# Display.net
KiCad netlist of a schematic drawn in Altium Designer
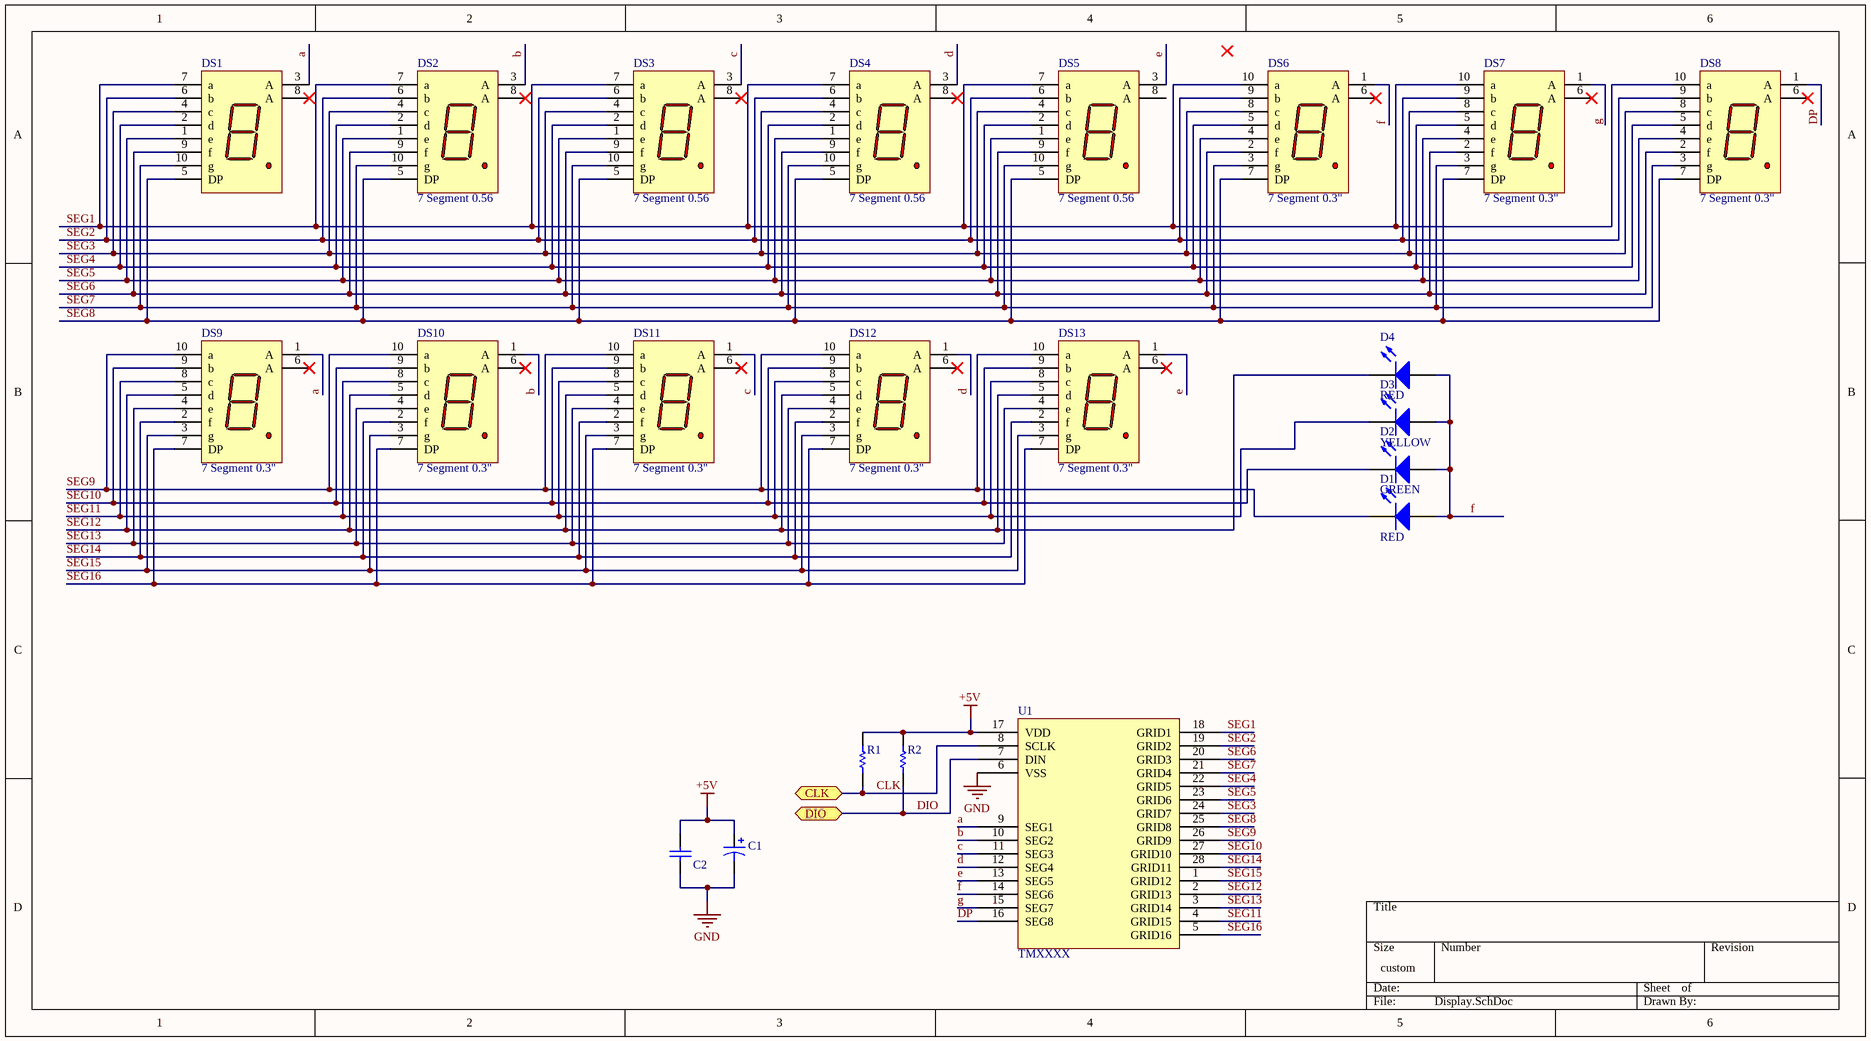
[diagram p0: Display.SchDoc]

(export (version "E")
  (design (tool "Eeschema 10.0.6"))
  (components
    (comp (ref "C1")
      (value "100uF/10V")
      (footprint "C10uF25V")
      (libsource (lib "Ravi") (part "Capacitor_Electrolytic"))
    )
    (comp (ref "C2")
      (value "0.1uF/10V")
      (footprint "C0603")
      (libsource (lib "Devices") (part "Capacitor_Ceramic"))
    )
    (comp (ref "D1") (value "RED") (footprint "LED-5mm") (libsource (lib "Ravi") (part "LED")))
    (comp (ref "D2") (value "GREEN") (footprint "LED-5mm") (libsource (lib "Ravi") (part "LED")))
    (comp (ref "D3") (value "YELLOW") (footprint "LED-5mm") (libsource (lib "Ravi") (part "LED")))
    (comp (ref "D4") (value "RED") (footprint "LED-5mm") (libsource (lib "Ravi") (part "LED")))
    (comp (ref "DS1")
      (value "7 Segment 0.56")
      (footprint "7Segment(0.56)")
      (libsource (lib "Ravi") (part "7 Segment_CA_0.56"))
    )
    (comp (ref "DS2")
      (value "7 Segment 0.56")
      (footprint "7Segment(0.56)")
      (libsource (lib "Ravi") (part "7 Segment_CA_0.56"))
    )
    (comp (ref "DS3")
      (value "7 Segment 0.56")
      (footprint "7Segment(0.56)")
      (libsource (lib "Ravi") (part "7 Segment_CA_0.56"))
    )
    (comp (ref "DS4")
      (value "7 Segment 0.56")
      (footprint "7Segment(0.56)")
      (libsource (lib "Ravi") (part "7 Segment_CA_0.56"))
    )
    (comp (ref "DS5")
      (value "7 Segment 0.56")
      (footprint "7Segment(0.56)")
      (libsource (lib "Ravi") (part "7 Segment_CA_0.56"))
    )
    (comp (ref "DS6")
      (value "7 Segment 0.3\"")
      (footprint "7Segment(0.36)")
      (libsource (lib "Ravi") (part "7 Segment_CA_0.36"))
    )
    (comp (ref "DS7")
      (value "7 Segment 0.3\"")
      (footprint "7Segment(0.36)")
      (libsource (lib "Ravi") (part "7 Segment_CA_0.36"))
    )
    (comp (ref "DS8")
      (value "7 Segment 0.3\"")
      (footprint "7Segment(0.36)")
      (libsource (lib "Ravi") (part "7 Segment_CA_0.36"))
    )
    (comp (ref "DS9")
      (value "7 Segment 0.3\"")
      (footprint "7Segment(0.36)")
      (libsource (lib "Ravi") (part "7 Segment_CA_0.36"))
    )
    (comp (ref "DS10")
      (value "7 Segment 0.3\"")
      (footprint "7Segment(0.36)")
      (libsource (lib "Ravi") (part "7 Segment_CA_0.36"))
    )
    (comp (ref "DS11")
      (value "7 Segment 0.3\"")
      (footprint "7Segment(0.36)")
      (libsource (lib "Ravi") (part "7 Segment_CA_0.36"))
    )
    (comp (ref "DS12")
      (value "7 Segment 0.3\"")
      (footprint "7Segment(0.36)")
      (libsource (lib "Ravi") (part "7 Segment_CA_0.36"))
    )
    (comp (ref "DS13")
      (value "7 Segment 0.3\"")
      (footprint "7Segment(0.36)")
      (libsource (lib "Ravi") (part "7 Segment_CA_0.36"))
    )
    (comp (ref "R1")
      (value "10K")
      (footprint "R0603")
      (description "Resistor")
      (fields (field (name "PUBLISHER") "Altium Limited"))
      (libsource (lib "Ravi") (part "Res1"))
    )
    (comp (ref "R2")
      (value "10K")
      (footprint "R0603")
      (description "Resistor")
      (fields (field (name "PUBLISHER") "Altium Limited"))
      (libsource (lib "Ravi") (part "Res1"))
    )
    (comp (ref "U1") (value "TMXXXX") (footprint "SOP28") (libsource (lib "Ravi") (part "TMXXXX")))
  )
  (nets
    (net (code "1") (name "+5V") (class "Default")
      (node (ref "C1") (pin "1") (pinfunction "1_1") (pintype "passive"))
      (node (ref "C2") (pin "2") (pinfunction "2_2") (pintype "passive"))
      (node (ref "R1") (pin "2") (pinfunction "2_2") (pintype "passive"))
      (node (ref "R2") (pin "2") (pinfunction "2_2") (pintype "passive"))
      (node (ref "U1") (pin "17") (pinfunction "VDD_17") (pintype "power_in"))
    )
    (net (code "2") (name "/CLK") (class "Default")
      (node (ref "R1") (pin "1") (pinfunction "1_1") (pintype "passive"))
      (node (ref "U1") (pin "8") (pinfunction "SCLK_8") (pintype "passive"))
    )
    (net (code "3") (name "/DIO") (class "Default")
      (node (ref "R2") (pin "1") (pinfunction "1_1") (pintype "passive"))
      (node (ref "U1") (pin "7") (pinfunction "DIN_7") (pintype "passive"))
    )
    (net (code "4") (name "/DP") (class "Default")
      (node (ref "DS8") (pin "1") (pinfunction "A_1") (pintype "passive"))
      (node (ref "U1") (pin "16") (pinfunction "SEG8_16") (pintype "open_collector"))
    )
    (net (code "5") (name "/SEG1") (class "Default")
      (node (ref "DS1") (pin "7") (pinfunction "a_7") (pintype "passive"))
      (node (ref "DS2") (pin "7") (pinfunction "a_7") (pintype "passive"))
      (node (ref "DS3") (pin "7") (pinfunction "a_7") (pintype "passive"))
      (node (ref "DS4") (pin "7") (pinfunction "a_7") (pintype "passive"))
      (node (ref "DS5") (pin "7") (pinfunction "a_7") (pintype "passive"))
      (node (ref "DS6") (pin "10") (pinfunction "a_10") (pintype "passive"))
      (node (ref "DS7") (pin "10") (pinfunction "a_10") (pintype "passive"))
      (node (ref "DS8") (pin "10") (pinfunction "a_10") (pintype "passive"))
      (node (ref "U1") (pin "18") (pinfunction "GRID1_18") (pintype "open_collector"))
    )
    (net (code "6") (name "/SEG2") (class "Default")
      (node (ref "DS1") (pin "6") (pinfunction "b_6") (pintype "passive"))
      (node (ref "DS2") (pin "6") (pinfunction "b_6") (pintype "passive"))
      (node (ref "DS3") (pin "6") (pinfunction "b_6") (pintype "passive"))
      (node (ref "DS4") (pin "6") (pinfunction "b_6") (pintype "passive"))
      (node (ref "DS5") (pin "6") (pinfunction "b_6") (pintype "passive"))
      (node (ref "DS6") (pin "9") (pinfunction "b_9") (pintype "passive"))
      (node (ref "DS7") (pin "9") (pinfunction "b_9") (pintype "passive"))
      (node (ref "DS8") (pin "9") (pinfunction "b_9") (pintype "passive"))
      (node (ref "U1") (pin "19") (pinfunction "GRID2_19") (pintype "open_collector"))
    )
    (net (code "7") (name "/SEG3") (class "Default")
      (node (ref "DS1") (pin "4") (pinfunction "c_4") (pintype "passive"))
      (node (ref "DS2") (pin "4") (pinfunction "c_4") (pintype "passive"))
      (node (ref "DS3") (pin "4") (pinfunction "c_4") (pintype "passive"))
      (node (ref "DS4") (pin "4") (pinfunction "c_4") (pintype "passive"))
      (node (ref "DS5") (pin "4") (pinfunction "c_4") (pintype "passive"))
      (node (ref "DS6") (pin "8") (pinfunction "c_8") (pintype "passive"))
      (node (ref "DS7") (pin "8") (pinfunction "c_8") (pintype "passive"))
      (node (ref "DS8") (pin "8") (pinfunction "c_8") (pintype "passive"))
      (node (ref "U1") (pin "24") (pinfunction "GRID7_24") (pintype "open_collector"))
    )
    (net (code "8") (name "/SEG4") (class "Default")
      (node (ref "DS1") (pin "2") (pinfunction "d_2") (pintype "passive"))
      (node (ref "DS2") (pin "2") (pinfunction "d_2") (pintype "passive"))
      (node (ref "DS3") (pin "2") (pinfunction "d_2") (pintype "passive"))
      (node (ref "DS4") (pin "2") (pinfunction "d_2") (pintype "passive"))
      (node (ref "DS5") (pin "2") (pinfunction "d_2") (pintype "passive"))
      (node (ref "DS6") (pin "5") (pinfunction "d_5") (pintype "passive"))
      (node (ref "DS7") (pin "5") (pinfunction "d_5") (pintype "passive"))
      (node (ref "DS8") (pin "5") (pinfunction "d_5") (pintype "passive"))
      (node (ref "U1") (pin "22") (pinfunction "GRID5_22") (pintype "open_collector"))
    )
    (net (code "9") (name "/SEG5") (class "Default")
      (node (ref "DS1") (pin "1") (pinfunction "e_1") (pintype "passive"))
      (node (ref "DS2") (pin "1") (pinfunction "e_1") (pintype "passive"))
      (node (ref "DS3") (pin "1") (pinfunction "e_1") (pintype "passive"))
      (node (ref "DS4") (pin "1") (pinfunction "e_1") (pintype "passive"))
      (node (ref "DS5") (pin "1") (pinfunction "e_1") (pintype "passive"))
      (node (ref "DS6") (pin "4") (pinfunction "e_4") (pintype "passive"))
      (node (ref "DS7") (pin "4") (pinfunction "e_4") (pintype "passive"))
      (node (ref "DS8") (pin "4") (pinfunction "e_4") (pintype "passive"))
      (node (ref "U1") (pin "23") (pinfunction "GRID6_23") (pintype "open_collector"))
    )
    (net (code "10") (name "/SEG6") (class "Default")
      (node (ref "DS1") (pin "9") (pinfunction "f_9") (pintype "passive"))
      (node (ref "DS2") (pin "9") (pinfunction "f_9") (pintype "passive"))
      (node (ref "DS3") (pin "9") (pinfunction "f_9") (pintype "passive"))
      (node (ref "DS4") (pin "9") (pinfunction "f_9") (pintype "passive"))
      (node (ref "DS5") (pin "9") (pinfunction "f_9") (pintype "passive"))
      (node (ref "DS6") (pin "2") (pinfunction "f_2") (pintype "passive"))
      (node (ref "DS7") (pin "2") (pinfunction "f_2") (pintype "passive"))
      (node (ref "DS8") (pin "2") (pinfunction "f_2") (pintype "passive"))
      (node (ref "U1") (pin "20") (pinfunction "GRID3_20") (pintype "open_collector"))
    )
    (net (code "11") (name "/SEG7") (class "Default")
      (node (ref "DS1") (pin "10") (pinfunction "g_10") (pintype "passive"))
      (node (ref "DS2") (pin "10") (pinfunction "g_10") (pintype "passive"))
      (node (ref "DS3") (pin "10") (pinfunction "g_10") (pintype "passive"))
      (node (ref "DS4") (pin "10") (pinfunction "g_10") (pintype "passive"))
      (node (ref "DS5") (pin "10") (pinfunction "g_10") (pintype "passive"))
      (node (ref "DS6") (pin "3") (pinfunction "g_3") (pintype "passive"))
      (node (ref "DS7") (pin "3") (pinfunction "g_3") (pintype "passive"))
      (node (ref "DS8") (pin "3") (pinfunction "g_3") (pintype "passive"))
      (node (ref "U1") (pin "21") (pinfunction "GRID4_21") (pintype "open_collector"))
    )
    (net (code "12") (name "/SEG8") (class "Default")
      (node (ref "DS1") (pin "5") (pinfunction "DP_5") (pintype "passive"))
      (node (ref "DS2") (pin "5") (pinfunction "DP_5") (pintype "passive"))
      (node (ref "DS3") (pin "5") (pinfunction "DP_5") (pintype "passive"))
      (node (ref "DS4") (pin "5") (pinfunction "DP_5") (pintype "passive"))
      (node (ref "DS5") (pin "5") (pinfunction "DP_5") (pintype "passive"))
      (node (ref "DS6") (pin "7") (pinfunction "DP_7") (pintype "passive"))
      (node (ref "DS7") (pin "7") (pinfunction "DP_7") (pintype "passive"))
      (node (ref "DS8") (pin "7") (pinfunction "DP_7") (pintype "passive"))
      (node (ref "U1") (pin "25") (pinfunction "GRID8_25") (pintype "open_collector"))
    )
    (net (code "13") (name "/SEG9") (class "Default")
      (node (ref "D1") (pin "2") (pinfunction "K_2") (pintype "passive"))
      (node (ref "DS10") (pin "10") (pinfunction "a_10") (pintype "passive"))
      (node (ref "DS11") (pin "10") (pinfunction "a_10") (pintype "passive"))
      (node (ref "DS12") (pin "10") (pinfunction "a_10") (pintype "passive"))
      (node (ref "DS13") (pin "10") (pinfunction "a_10") (pintype "passive"))
      (node (ref "DS9") (pin "10") (pinfunction "a_10") (pintype "passive"))
      (node (ref "U1") (pin "26") (pinfunction "GRID9_26") (pintype "open_collector"))
    )
    (net (code "14") (name "/SEG10") (class "Default")
      (node (ref "D2") (pin "2") (pinfunction "K_2") (pintype "passive"))
      (node (ref "DS10") (pin "9") (pinfunction "b_9") (pintype "passive"))
      (node (ref "DS11") (pin "9") (pinfunction "b_9") (pintype "passive"))
      (node (ref "DS12") (pin "9") (pinfunction "b_9") (pintype "passive"))
      (node (ref "DS13") (pin "9") (pinfunction "b_9") (pintype "passive"))
      (node (ref "DS9") (pin "9") (pinfunction "b_9") (pintype "passive"))
      (node (ref "U1") (pin "27") (pinfunction "GRID10_27") (pintype "open_collector"))
    )
    (net (code "15") (name "/SEG11") (class "Default")
      (node (ref "D3") (pin "2") (pinfunction "K_2") (pintype "passive"))
      (node (ref "DS10") (pin "8") (pinfunction "c_8") (pintype "passive"))
      (node (ref "DS11") (pin "8") (pinfunction "c_8") (pintype "passive"))
      (node (ref "DS12") (pin "8") (pinfunction "c_8") (pintype "passive"))
      (node (ref "DS13") (pin "8") (pinfunction "c_8") (pintype "passive"))
      (node (ref "DS9") (pin "8") (pinfunction "c_8") (pintype "passive"))
      (node (ref "U1") (pin "4") (pinfunction "GRID15_4") (pintype "open_collector"))
    )
    (net (code "16") (name "/SEG12") (class "Default")
      (node (ref "D4") (pin "2") (pinfunction "K_2") (pintype "passive"))
      (node (ref "DS10") (pin "5") (pinfunction "d_5") (pintype "passive"))
      (node (ref "DS11") (pin "5") (pinfunction "d_5") (pintype "passive"))
      (node (ref "DS12") (pin "5") (pinfunction "d_5") (pintype "passive"))
      (node (ref "DS13") (pin "5") (pinfunction "d_5") (pintype "passive"))
      (node (ref "DS9") (pin "5") (pinfunction "d_5") (pintype "passive"))
      (node (ref "U1") (pin "2") (pinfunction "GRID13_2") (pintype "open_collector"))
    )
    (net (code "17") (name "/SEG13") (class "Default")
      (node (ref "DS10") (pin "4") (pinfunction "e_4") (pintype "passive"))
      (node (ref "DS11") (pin "4") (pinfunction "e_4") (pintype "passive"))
      (node (ref "DS12") (pin "4") (pinfunction "e_4") (pintype "passive"))
      (node (ref "DS13") (pin "4") (pinfunction "e_4") (pintype "passive"))
      (node (ref "DS9") (pin "4") (pinfunction "e_4") (pintype "passive"))
      (node (ref "U1") (pin "3") (pinfunction "GRID14_3") (pintype "open_collector"))
    )
    (net (code "18") (name "/SEG14") (class "Default")
      (node (ref "DS10") (pin "2") (pinfunction "f_2") (pintype "passive"))
      (node (ref "DS11") (pin "2") (pinfunction "f_2") (pintype "passive"))
      (node (ref "DS12") (pin "2") (pinfunction "f_2") (pintype "passive"))
      (node (ref "DS13") (pin "2") (pinfunction "f_2") (pintype "passive"))
      (node (ref "DS9") (pin "2") (pinfunction "f_2") (pintype "passive"))
      (node (ref "U1") (pin "28") (pinfunction "GRID11_28") (pintype "open_collector"))
    )
    (net (code "19") (name "/SEG15") (class "Default")
      (node (ref "DS10") (pin "3") (pinfunction "g_3") (pintype "passive"))
      (node (ref "DS11") (pin "3") (pinfunction "g_3") (pintype "passive"))
      (node (ref "DS12") (pin "3") (pinfunction "g_3") (pintype "passive"))
      (node (ref "DS13") (pin "3") (pinfunction "g_3") (pintype "passive"))
      (node (ref "DS9") (pin "3") (pinfunction "g_3") (pintype "passive"))
      (node (ref "U1") (pin "1") (pinfunction "GRID12_1") (pintype "open_collector"))
    )
    (net (code "20") (name "/SEG16") (class "Default")
      (node (ref "DS10") (pin "7") (pinfunction "DP_7") (pintype "passive"))
      (node (ref "DS11") (pin "7") (pinfunction "DP_7") (pintype "passive"))
      (node (ref "DS12") (pin "7") (pinfunction "DP_7") (pintype "passive"))
      (node (ref "DS13") (pin "7") (pinfunction "DP_7") (pintype "passive"))
      (node (ref "DS9") (pin "7") (pinfunction "DP_7") (pintype "passive"))
      (node (ref "U1") (pin "5") (pinfunction "GRID16_5") (pintype "open_collector"))
    )
    (net (code "21") (name "/a") (class "Default")
      (node (ref "DS1") (pin "3") (pinfunction "A_3") (pintype "passive"))
      (node (ref "DS9") (pin "1") (pinfunction "A_1") (pintype "passive"))
      (node (ref "U1") (pin "9") (pinfunction "SEG1_9") (pintype "open_collector"))
    )
    (net (code "22") (name "/b") (class "Default")
      (node (ref "DS10") (pin "1") (pinfunction "A_1") (pintype "passive"))
      (node (ref "DS2") (pin "3") (pinfunction "A_3") (pintype "passive"))
      (node (ref "U1") (pin "10") (pinfunction "SEG2_10") (pintype "open_collector"))
    )
    (net (code "23") (name "/c") (class "Default")
      (node (ref "DS11") (pin "1") (pinfunction "A_1") (pintype "passive"))
      (node (ref "DS3") (pin "3") (pinfunction "A_3") (pintype "passive"))
      (node (ref "U1") (pin "11") (pinfunction "SEG3_11") (pintype "open_collector"))
    )
    (net (code "24") (name "/d") (class "Default")
      (node (ref "DS12") (pin "1") (pinfunction "A_1") (pintype "passive"))
      (node (ref "DS4") (pin "3") (pinfunction "A_3") (pintype "passive"))
      (node (ref "U1") (pin "12") (pinfunction "SEG4_12") (pintype "open_collector"))
    )
    (net (code "25") (name "/e") (class "Default")
      (node (ref "DS13") (pin "1") (pinfunction "A_1") (pintype "passive"))
      (node (ref "DS5") (pin "3") (pinfunction "A_3") (pintype "passive"))
      (node (ref "U1") (pin "13") (pinfunction "SEG5_13") (pintype "open_collector"))
    )
    (net (code "26") (name "/f") (class "Default")
      (node (ref "D1") (pin "1") (pinfunction "A_1") (pintype "passive"))
      (node (ref "D2") (pin "1") (pinfunction "A_1") (pintype "passive"))
      (node (ref "D3") (pin "1") (pinfunction "A_1") (pintype "passive"))
      (node (ref "D4") (pin "1") (pinfunction "A_1") (pintype "passive"))
      (node (ref "DS6") (pin "1") (pinfunction "A_1") (pintype "passive"))
      (node (ref "U1") (pin "14") (pinfunction "SEG6_14") (pintype "open_collector"))
    )
    (net (code "27") (name "/g") (class "Default")
      (node (ref "DS7") (pin "1") (pinfunction "A_1") (pintype "passive"))
      (node (ref "U1") (pin "15") (pinfunction "SEG7_15") (pintype "open_collector"))
    )
    (net (code "28") (name "GND") (class "Default")
      (node (ref "C1") (pin "2") (pinfunction "2_2") (pintype "passive"))
      (node (ref "C2") (pin "1") (pinfunction "1_1") (pintype "passive"))
      (node (ref "U1") (pin "6") (pinfunction "VSS_6") (pintype "power_in"))
    )
    (net (code "29") (name "unconnected-(DS1-A-Pad8)") (class "Default")
      (node (ref "DS1") (pin "8") (pinfunction "A_8") (pintype "passive+no_connect"))
    )
    (net (code "30") (name "unconnected-(DS2-A-Pad8)") (class "Default")
      (node (ref "DS2") (pin "8") (pinfunction "A_8") (pintype "passive+no_connect"))
    )
    (net (code "31") (name "unconnected-(DS3-A-Pad8)") (class "Default")
      (node (ref "DS3") (pin "8") (pinfunction "A_8") (pintype "passive+no_connect"))
    )
    (net (code "32") (name "unconnected-(DS4-A-Pad8)") (class "Default")
      (node (ref "DS4") (pin "8") (pinfunction "A_8") (pintype "passive+no_connect"))
    )
    (net (code "33") (name "unconnected-(DS5-A-Pad8)") (class "Default")
      (node (ref "DS5") (pin "8") (pinfunction "A_8") (pintype "passive"))
    )
    (net (code "34") (name "unconnected-(DS6-A-Pad6)") (class "Default")
      (node (ref "DS6") (pin "6") (pinfunction "A_6") (pintype "passive+no_connect"))
    )
    (net (code "35") (name "unconnected-(DS7-A-Pad6)") (class "Default")
      (node (ref "DS7") (pin "6") (pinfunction "A_6") (pintype "passive+no_connect"))
    )
    (net (code "36") (name "unconnected-(DS8-A-Pad6)") (class "Default")
      (node (ref "DS8") (pin "6") (pinfunction "A_6") (pintype "passive+no_connect"))
    )
    (net (code "37") (name "unconnected-(DS9-A-Pad6)") (class "Default")
      (node (ref "DS9") (pin "6") (pinfunction "A_6") (pintype "passive+no_connect"))
    )
    (net (code "38") (name "unconnected-(DS10-A-Pad6)") (class "Default")
      (node (ref "DS10") (pin "6") (pinfunction "A_6") (pintype "passive+no_connect"))
    )
    (net (code "39") (name "unconnected-(DS11-A-Pad6)") (class "Default")
      (node (ref "DS11") (pin "6") (pinfunction "A_6") (pintype "passive+no_connect"))
    )
    (net (code "40") (name "unconnected-(DS12-A-Pad6)") (class "Default")
      (node (ref "DS12") (pin "6") (pinfunction "A_6") (pintype "passive+no_connect"))
    )
    (net (code "41") (name "unconnected-(DS13-A-Pad6)") (class "Default")
      (node (ref "DS13") (pin "6") (pinfunction "A_6") (pintype "passive+no_connect"))
    )
  )
)
